# motherboard.net
KiCad netlist of a schematic drawn in Altium Designer
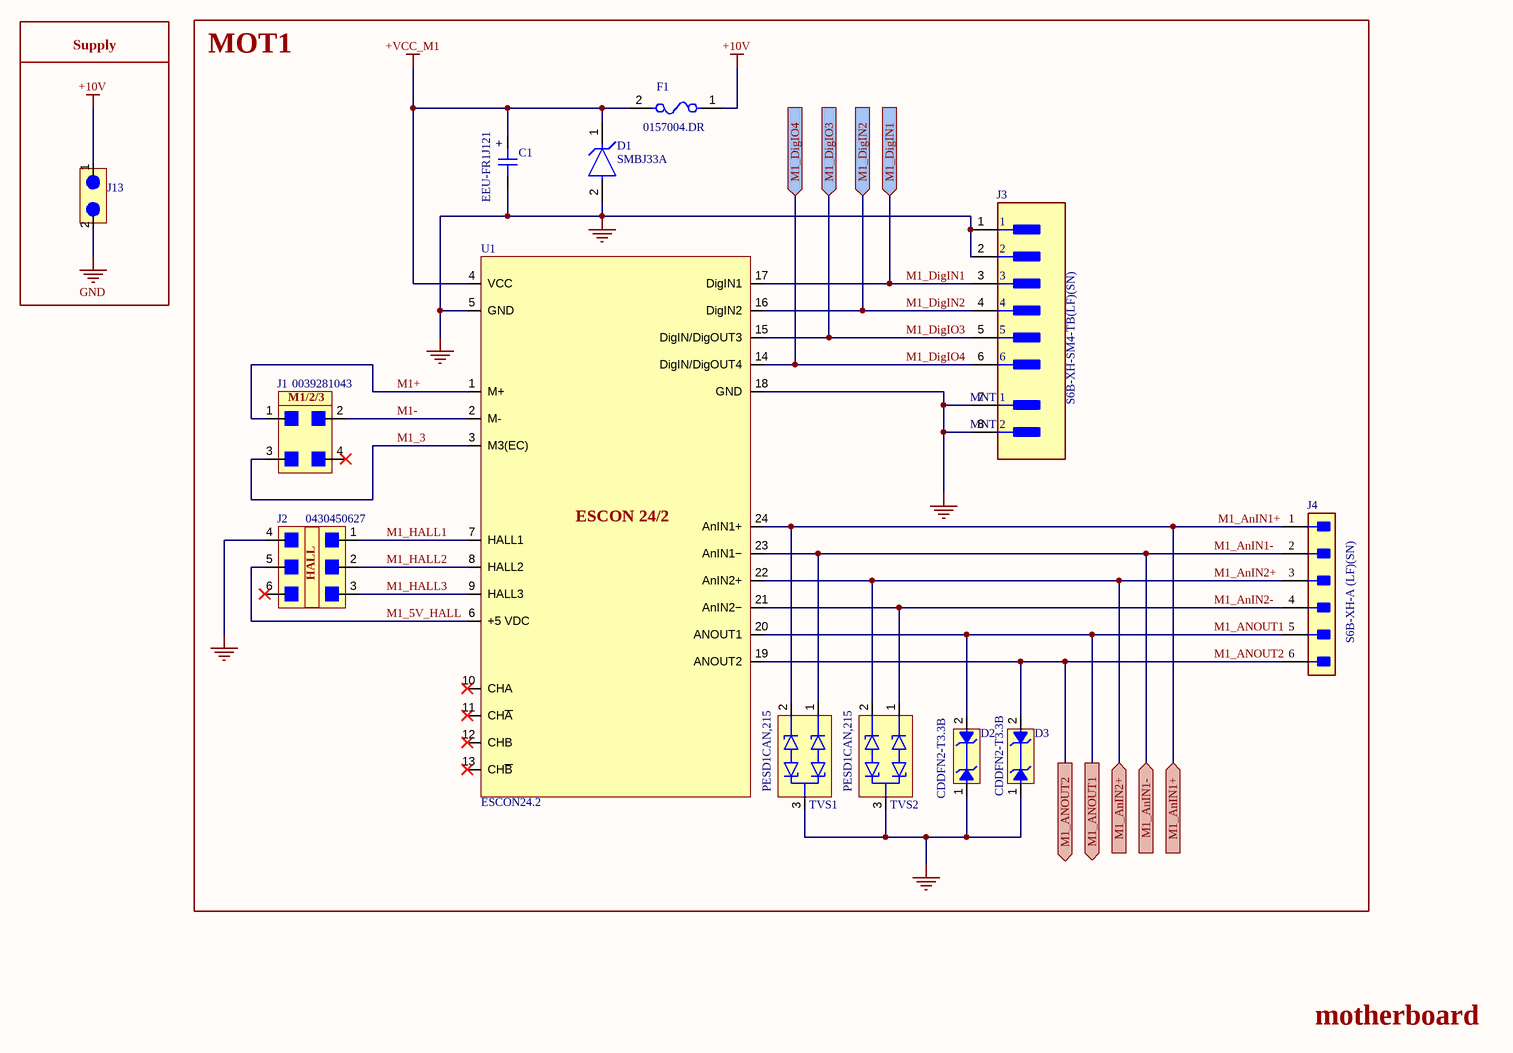
[diagram p0: motherboard.SchDoc]

(export (version "E")
  (design (tool "Eeschema 10.0.6"))
  (components
    (comp (ref "C1")
      (value "EEU-FR1J121")
      (footprint "CAP_THT_RAD_5mm")
      (description "CAP, ELEC, 120 µF 63 V Aluminum Electrolytic Capacitors Radial, Can 8000 Hrs @ 105°C")
      (libsource (lib "SchematicLib") (part "EEU-FR1J121"))
    )
    (comp (ref "D1")
      (value "SMBJ33A")
      (footprint "DO-214AA, SMB")
      (description "TVS DIODE 33V 53.3V DO214AA")
      (fields
        (field (name "MANUFACTURER") "Littelfuse Inc")
        (field (name "OCTOPART") "https://octopart.com/smbj33a-littelfuse-350829")
      )
      (libsource (lib "SchematicLib") (part "SMBJ33A"))
    )
    (comp (ref "D2")
      (value "CDDFN2-T3.3B")
      (footprint "D_0402")
      (description "8V Clamp 5A (8/20Âµs) Ipp Tvs Diode Surface Mount 2-DFN (1x0.6)")
      (fields (field (name "MF") "Bourns"))
      (libsource (lib "SchematicLib") (part "CDDFN2-T3.3B"))
    )
    (comp (ref "D3")
      (value "CDDFN2-T3.3B")
      (footprint "D_0402")
      (description "8V Clamp 5A (8/20Âµs) Ipp Tvs Diode Surface Mount 2-DFN (1x0.6)")
      (fields (field (name "MF") "Bourns"))
      (libsource (lib "SchematicLib") (part "CDDFN2-T3.3B"))
    )
    (comp (ref "F1")
      (value "0157004.DR")
      (footprint "NANO2")
      (libsource (lib "SchematicLib") (part "0157004.DR"))
    )
    (comp (ref "J1")
      (value "0039281043")
      (footprint "4.20mm Dual Row 4 Circuit CONN")
      (description "Molex Connector Header Through Hole 4 position 0.165\" (4.20mm)")
      (libsource (lib "SchematicLib") (part "0039281043"))
    )
    (comp (ref "J2")
      (value "0430450627")
      (footprint "3.00MM DUAL ROW 6 Circuit CONN")
      (description "Molex Connector Header Through Hole 6 position 0.118\" (3.00mm)")
      (libsource (lib "SchematicLib") (part "0430450627"))
    )
    (comp (ref "J3")
      (value "S6B-XH-SM4-TB(LF)(SN)")
      (footprint "S6B-XH-SM4-TB")
      (description "CONN HEADER SMD R/A 6POS 2.5MM")
      (libsource (lib "SchematicLib") (part "S6B-XH-SM4-TB"))
    )
    (comp (ref "J4")
      (value "S6B-XH-A (LF)(SN)")
      (footprint "JST-XH-6PIN_RA")
      (description "CONN HEADER THT R/A 6POS 2.5MM")
      (libsource (lib "SchematicLib") (part "S6B-XH-A (LF)(SN)"))
    )
    (comp (ref "J13")
      (value "POWER_CONN")
      (footprint "POWER")
      (libsource (lib "SchematicLib") (part "Power_CONN_NO_BOM"))
    )
    (comp (ref "TVS1")
      (value "PESD1CAN,215")
      (footprint "SOT23")
      (description "70V Clamp 3A (8/20Âµs) Ipp Tvs Diode Surface Mount TO-236AB")
      (fields (field (name "MF") "Nexperia USA Inc."))
      (libsource (lib "SchematicLib") (part "PESD1CAN,215"))
    )
    (comp (ref "TVS2")
      (value "PESD1CAN,215")
      (footprint "SOT23")
      (description "70V Clamp 3A (8/20Âµs) Ipp Tvs Diode Surface Mount TO-236AB")
      (fields (field (name "MF") "Nexperia USA Inc."))
      (libsource (lib "SchematicLib") (part "PESD1CAN,215"))
    )
    (comp (ref "U1")
      (value "ESCON24.2")
      (footprint "ESCON24.2")
      (description "ESCON24.2 Motor Controller Module")
      (libsource (lib "SchematicLib") (part "ESCON24.2"))
    )
  )
  (nets
    (net (code "1") (name "+10V") (class "Default")
      (node (ref "F1") (pin "1") (pinfunction "1_1") (pintype "passive"))
      (node (ref "J13") (pin "1") (pinfunction "+10V_1") (pintype "passive"))
    )
    (net (code "2") (name "+VCC_M1") (class "Default")
      (node (ref "C1") (pin "1") (pinfunction "1_1") (pintype "passive"))
      (node (ref "D1") (pin "1") (pinfunction "C_1") (pintype "passive"))
      (node (ref "F1") (pin "2") (pinfunction "2_2") (pintype "passive"))
      (node (ref "U1") (pin "4") (pinfunction "VCC_4") (pintype "passive"))
    )
    (net (code "3") (name "/M1+") (class "Default")
      (node (ref "J1") (pin "1") (pinfunction "1_1") (pintype "passive"))
      (node (ref "U1") (pin "1") (pinfunction "M+_1") (pintype "passive"))
    )
    (net (code "4") (name "/M1-") (class "Default")
      (node (ref "J1") (pin "2") (pinfunction "2_2") (pintype "passive"))
      (node (ref "U1") (pin "2") (pinfunction "M-_2") (pintype "passive"))
    )
    (net (code "5") (name "/M1_3") (class "Default")
      (node (ref "J1") (pin "3") (pinfunction "3_3") (pintype "passive"))
      (node (ref "U1") (pin "3") (pinfunction "M3(EC)_3") (pintype "passive"))
    )
    (net (code "6") (name "/M1_5V_HALL") (class "Default")
      (node (ref "J2") (pin "5") (pinfunction "5_5") (pintype "passive"))
      (node (ref "U1") (pin "6") (pinfunction "+5_VDC_6") (pintype "passive"))
    )
    (net (code "7") (name "/M1_ANOUT1") (class "Default")
      (node (ref "D2") (pin "2") (pinfunction "2_2") (pintype "passive"))
      (node (ref "J4") (pin "5") (pinfunction "5_5") (pintype "passive"))
      (node (ref "U1") (pin "20") (pinfunction "ANOUT1_20") (pintype "passive"))
    )
    (net (code "8") (name "/M1_ANOUT2") (class "Default")
      (node (ref "D3") (pin "2") (pinfunction "2_2") (pintype "passive"))
      (node (ref "J4") (pin "6") (pinfunction "6_6") (pintype "passive"))
      (node (ref "U1") (pin "19") (pinfunction "ANOUT2_19") (pintype "passive"))
    )
    (net (code "9") (name "/M1_AnIN1+") (class "Default")
      (node (ref "J4") (pin "1") (pinfunction "1_1") (pintype "passive"))
      (node (ref "TVS1") (pin "2") (pinfunction "C2_2") (pintype "passive"))
      (node (ref "U1") (pin "24") (pinfunction "AnIN1+_24") (pintype "passive"))
    )
    (net (code "10") (name "/M1_AnIN1-") (class "Default")
      (node (ref "J4") (pin "2") (pinfunction "2_2") (pintype "passive"))
      (node (ref "TVS1") (pin "1") (pinfunction "C1_1") (pintype "passive"))
      (node (ref "U1") (pin "23") (pinfunction "AnIN1−_23") (pintype "passive"))
    )
    (net (code "11") (name "/M1_AnIN2+") (class "Default")
      (node (ref "J4") (pin "3") (pinfunction "3_3") (pintype "passive"))
      (node (ref "TVS2") (pin "2") (pinfunction "C2_2") (pintype "passive"))
      (node (ref "U1") (pin "22") (pinfunction "AnIN2+_22") (pintype "passive"))
    )
    (net (code "12") (name "/M1_AnIN2-") (class "Default")
      (node (ref "J4") (pin "4") (pinfunction "4_4") (pintype "passive"))
      (node (ref "TVS2") (pin "1") (pinfunction "C1_1") (pintype "passive"))
      (node (ref "U1") (pin "21") (pinfunction "AnIN2−_21") (pintype "passive"))
    )
    (net (code "13") (name "/M1_DigIN1") (class "Default")
      (node (ref "J3") (pin "3") (pinfunction "3_3") (pintype "passive"))
      (node (ref "U1") (pin "17") (pinfunction "DigIN1_17") (pintype "passive"))
    )
    (net (code "14") (name "/M1_DigIN2") (class "Default")
      (node (ref "J3") (pin "4") (pinfunction "4_4") (pintype "passive"))
      (node (ref "U1") (pin "16") (pinfunction "DigIN2_16") (pintype "passive"))
    )
    (net (code "15") (name "/M1_DigIO3") (class "Default")
      (node (ref "J3") (pin "5") (pinfunction "5_5") (pintype "passive"))
      (node (ref "U1") (pin "15") (pinfunction "DigIN/DigOUT3_15") (pintype "passive"))
    )
    (net (code "16") (name "/M1_DigIO4") (class "Default")
      (node (ref "J3") (pin "6") (pinfunction "6_6") (pintype "passive"))
      (node (ref "U1") (pin "14") (pinfunction "DigIN/DigOUT4_14") (pintype "passive"))
    )
    (net (code "17") (name "/M1_HALL1") (class "Default")
      (node (ref "J2") (pin "1") (pinfunction "1_1") (pintype "passive"))
      (node (ref "U1") (pin "7") (pinfunction "HALL1_7") (pintype "passive"))
    )
    (net (code "18") (name "/M1_HALL2") (class "Default")
      (node (ref "J2") (pin "2") (pinfunction "2_2") (pintype "passive"))
      (node (ref "U1") (pin "8") (pinfunction "HALL2_8") (pintype "passive"))
    )
    (net (code "19") (name "/M1_HALL3") (class "Default")
      (node (ref "J2") (pin "3") (pinfunction "3_3") (pintype "passive"))
      (node (ref "U1") (pin "9") (pinfunction "HALL3_9") (pintype "passive"))
    )
    (net (code "20") (name "GND") (class "Default")
      (node (ref "C1") (pin "2") (pinfunction "2_2") (pintype "passive"))
      (node (ref "D1") (pin "2") (pinfunction "A_2") (pintype "passive"))
      (node (ref "D2") (pin "1") (pinfunction "1_1") (pintype "passive"))
      (node (ref "D3") (pin "1") (pinfunction "1_1") (pintype "passive"))
      (node (ref "J13") (pin "2") (pinfunction "GND_2") (pintype "passive"))
      (node (ref "J2") (pin "4") (pinfunction "4_4") (pintype "passive"))
      (node (ref "J3") (pin "1") (pinfunction "1_1") (pintype "passive"))
      (node (ref "J3") (pin "2") (pinfunction "2_2") (pintype "passive"))
      (node (ref "J3") (pin "7") (pinfunction "MNT_1_7") (pintype "passive"))
      (node (ref "J3") (pin "8") (pinfunction "MNT_2_8") (pintype "passive"))
      (node (ref "TVS1") (pin "3") (pinfunction "CC_3") (pintype "passive"))
      (node (ref "TVS2") (pin "3") (pinfunction "CC_3") (pintype "passive"))
      (node (ref "U1") (pin "18") (pinfunction "GND_18") (pintype "passive"))
      (node (ref "U1") (pin "5") (pinfunction "GND_5") (pintype "passive"))
    )
    (net (code "21") (name "unconnected-(J1-Pad4)") (class "Default")
      (node (ref "J1") (pin "4") (pinfunction "4_4") (pintype "passive+no_connect"))
    )
    (net (code "22") (name "unconnected-(J2-Pad6)") (class "Default")
      (node (ref "J2") (pin "6") (pinfunction "6_6") (pintype "passive+no_connect"))
    )
    (net (code "23") (name "unconnected-(U1-CHA-Pad10)") (class "Default")
      (node (ref "U1") (pin "10") (pinfunction "CHA_10") (pintype "passive+no_connect"))
    )
    (net (code "24") (name "unconnected-(U1-CHB-Pad12)") (class "Default")
      (node (ref "U1") (pin "12") (pinfunction "CHB_12") (pintype "passive+no_connect"))
    )
    (net (code "25") (name "unconnected-(U1-CH~{A}-Pad11)") (class "Default")
      (node (ref "U1") (pin "11") (pinfunction "CH~{A}_11") (pintype "passive+no_connect"))
    )
    (net (code "26") (name "unconnected-(U1-CH~{B}-Pad13)") (class "Default")
      (node (ref "U1") (pin "13") (pinfunction "CH~{B}_13") (pintype "passive+no_connect"))
    )
  )
)
